# ScoreBoard-V2.net
KiCad netlist of a schematic drawn in EAGLE
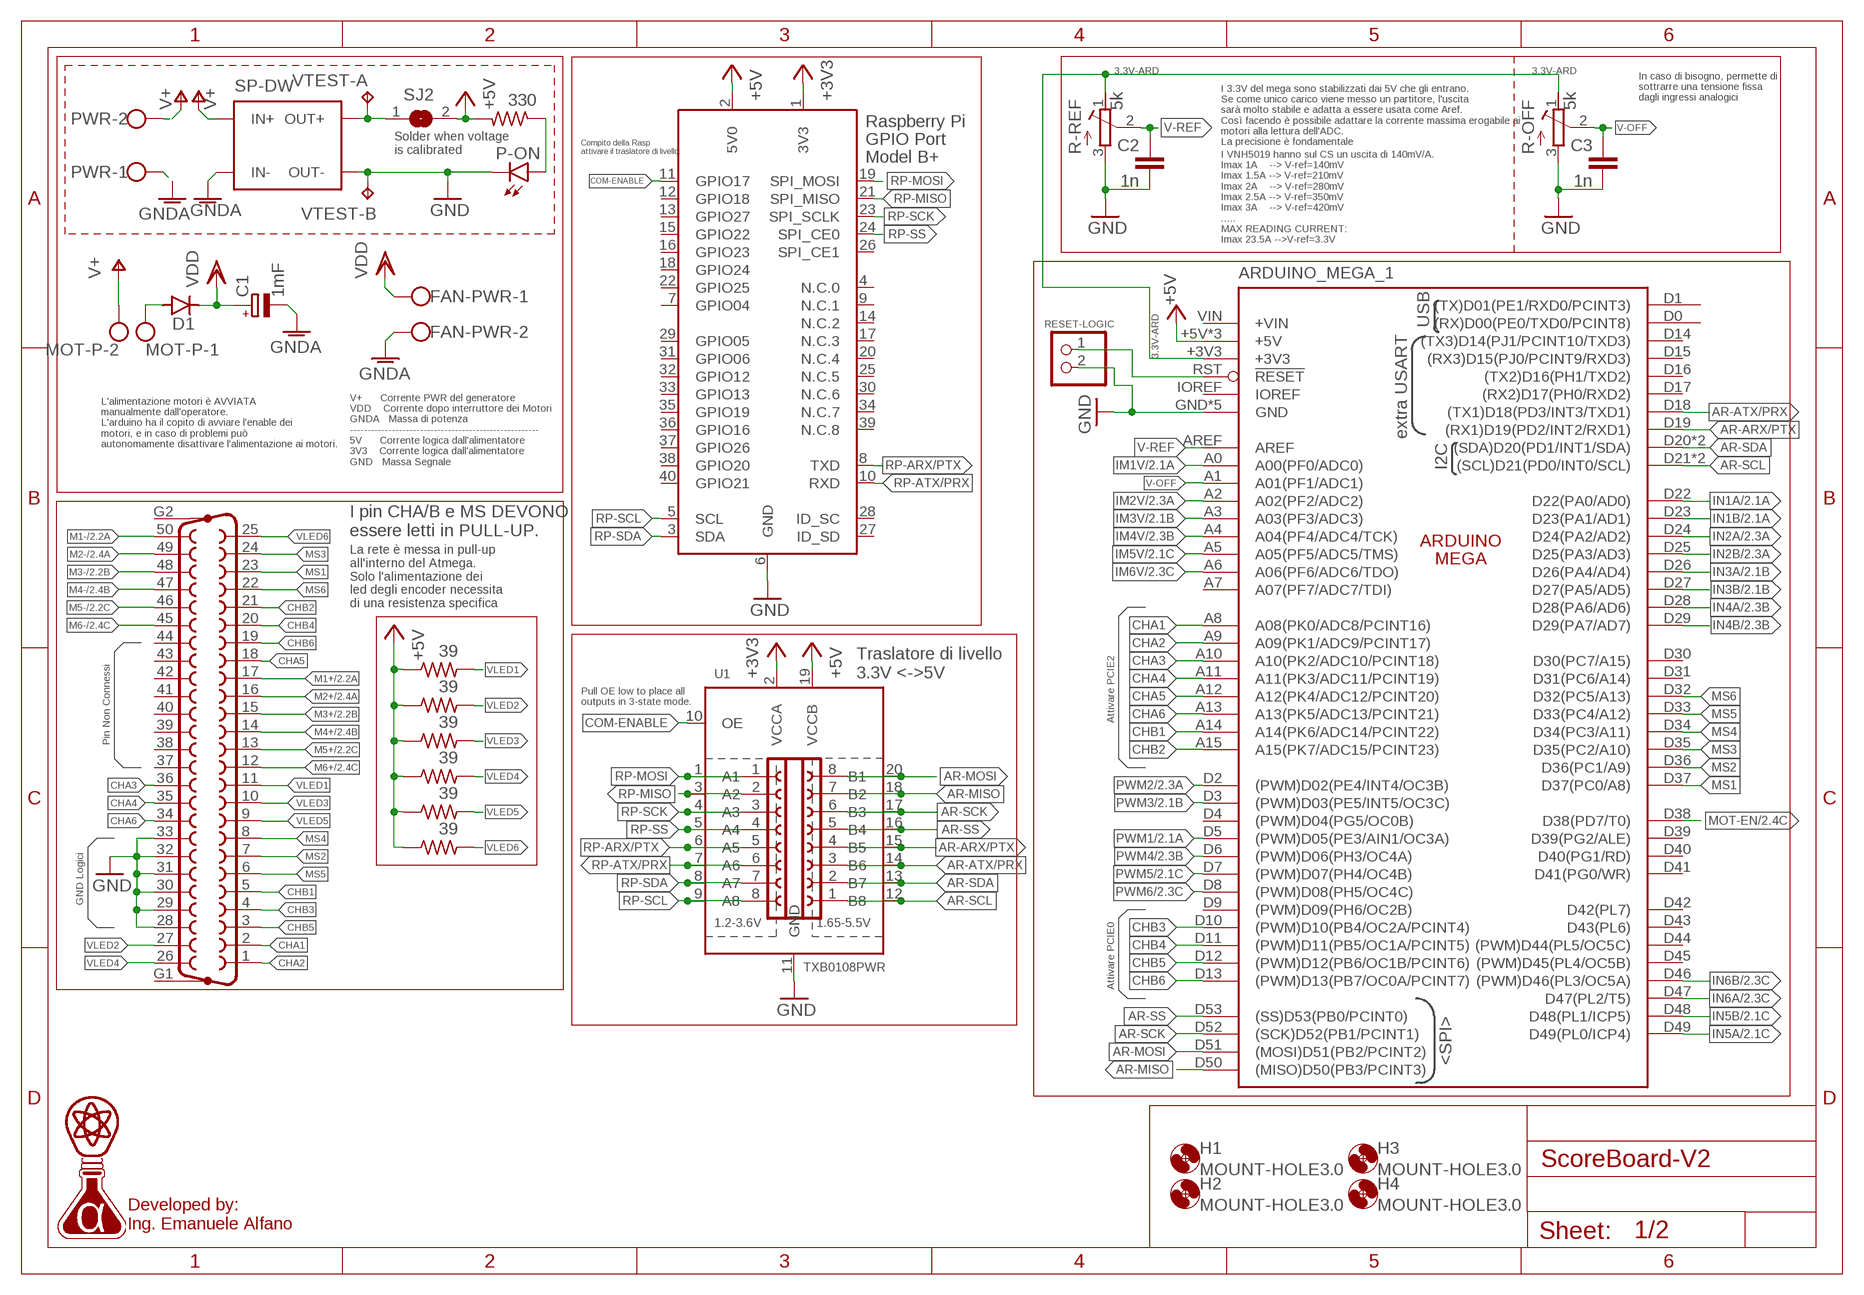
[diagram p0: schematic, sheet 1]
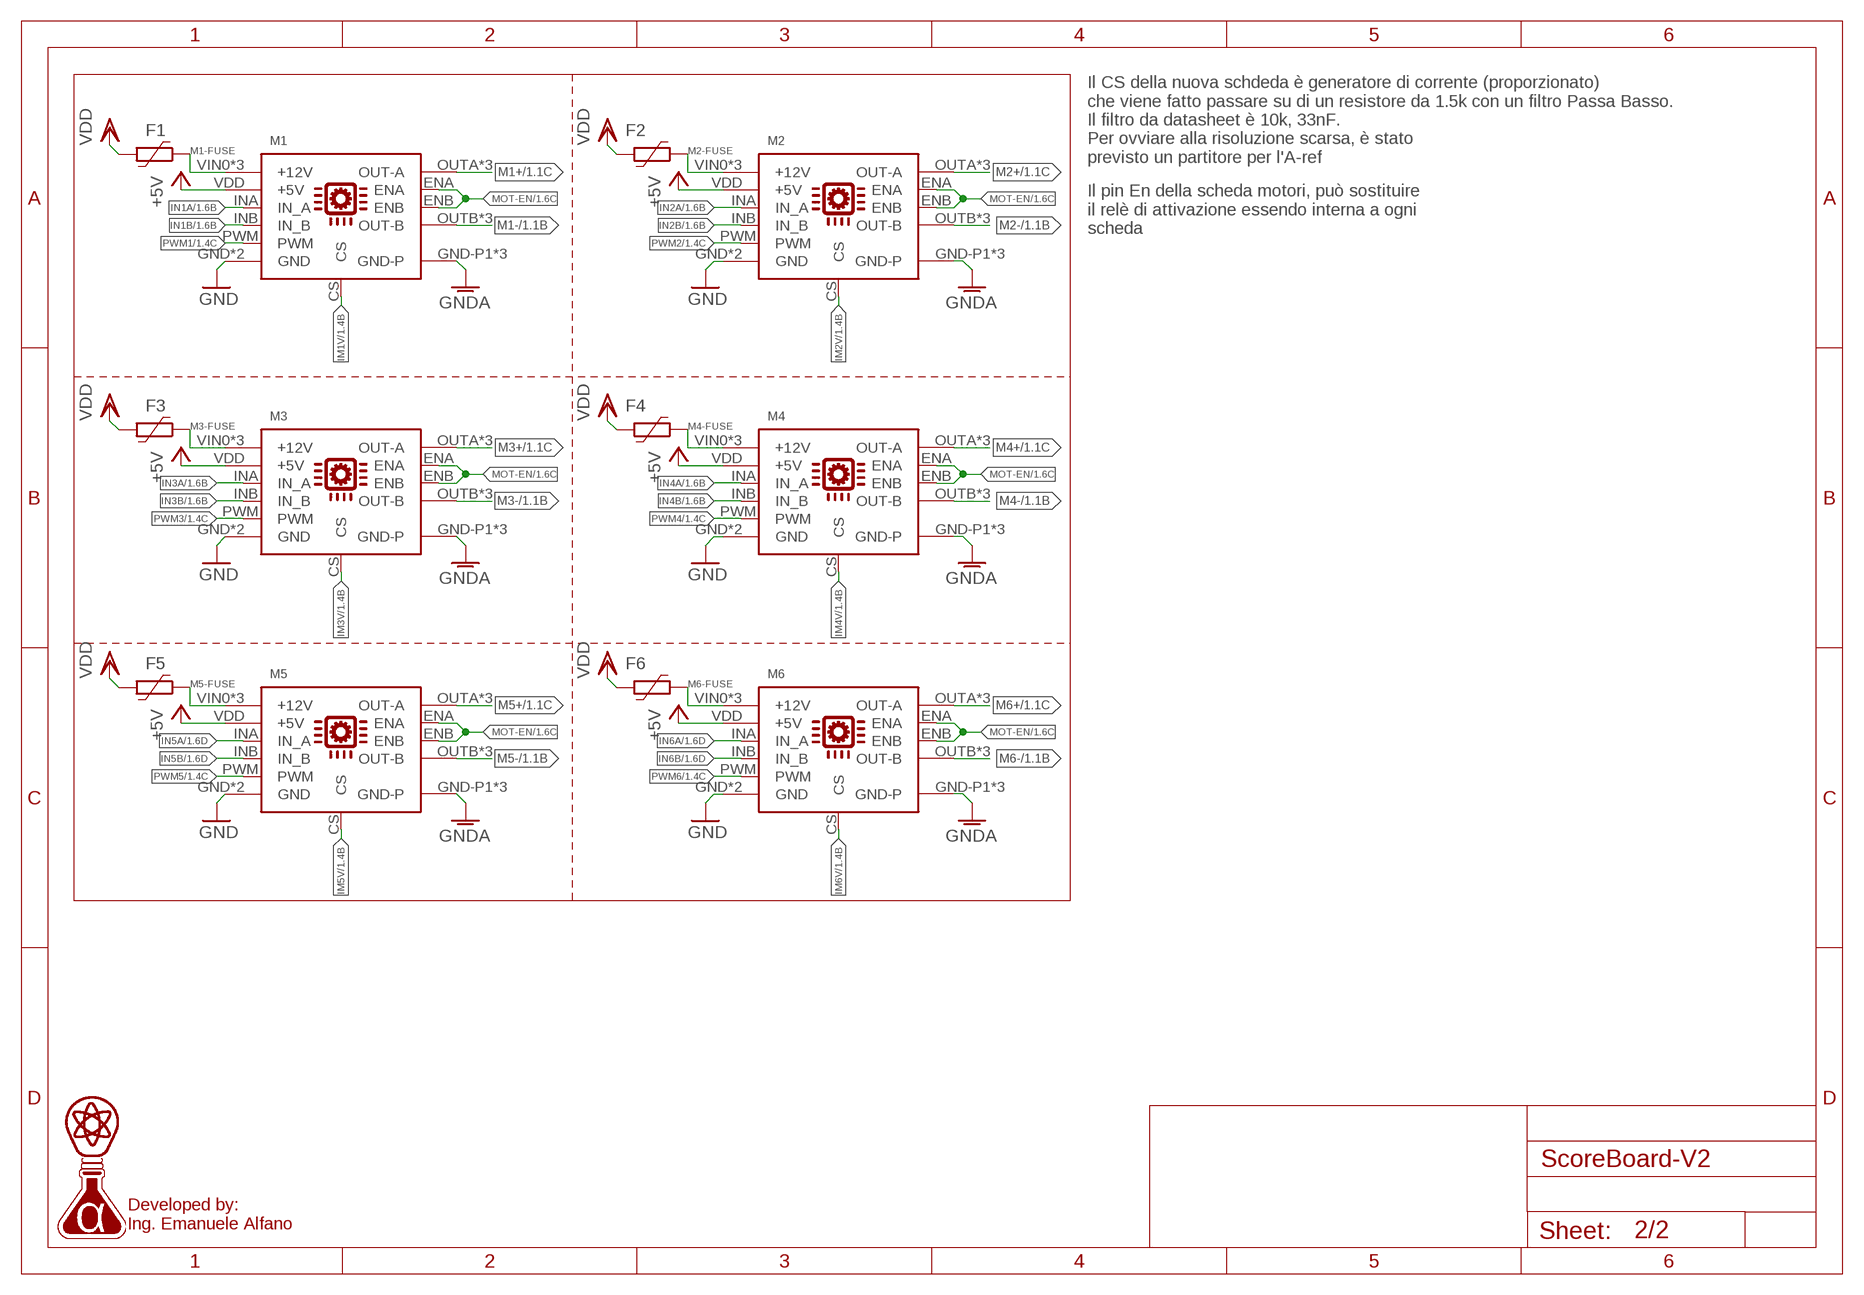
[diagram p1: schematic, sheet 2]

(export (version "E")
  (design (tool "Eeschema 10.0.6"))
  (components
    (comp (ref "ARDUINO_MEGA_1")
      (value "MEGA_ARDUINONO-HOLE")
      (footprint "eagle-import:MEGA-NO-HOLE")
      (libsource (lib "eagle-import") (part "MEGA_ARDUINONO-HOLE"))
    )
    (comp (ref "C1")
      (value "1mF")
      (footprint "eagle-import:E5-13")
      (libsource (lib "eagle-import") (part "CPOL-EUE5-13"))
    )
    (comp (ref "C2")
      (value "1n")
      (footprint "eagle-import:C025-024X044")
      (libsource (lib "eagle-import") (part "C-EU025-024X044"))
    )
    (comp (ref "C3")
      (value "1n")
      (footprint "eagle-import:C025-024X044")
      (libsource (lib "eagle-import") (part "C-EU025-024X044"))
    )
    (comp (ref "D-SUB50")
      (value "F50VP")
      (footprint "eagle-import:F50VP")
      (libsource (lib "eagle-import") (part "F50VP"))
    )
    (comp (ref "D1")
      (value "ES2D")
      (footprint "eagle-import:SMB")
      (libsource (lib "eagle-import") (part "ES2D"))
    )
    (comp (ref "FAN-PWR")
      (value "W237-102")
      (footprint "eagle-import:W237-102")
      (fields (field (name "MPN") "237-102"))
      (libsource (lib "eagle-import") (part "W237-102"))
    )
    (comp (ref "H1")
      (value "MOUNT-HOLE3.0")
      (footprint "eagle-import:3,0")
      (libsource (lib "eagle-import") (part "MOUNT-HOLE3.0"))
    )
    (comp (ref "H2")
      (value "MOUNT-HOLE3.0")
      (footprint "eagle-import:3,0")
      (libsource (lib "eagle-import") (part "MOUNT-HOLE3.0"))
    )
    (comp (ref "H3")
      (value "MOUNT-HOLE3.0")
      (footprint "eagle-import:3,0")
      (libsource (lib "eagle-import") (part "MOUNT-HOLE3.0"))
    )
    (comp (ref "H4")
      (value "MOUNT-HOLE3.0")
      (footprint "eagle-import:3,0")
      (libsource (lib "eagle-import") (part "MOUNT-HOLE3.0"))
    )
    (comp (ref "MOT-P")
      (value "W237-102")
      (footprint "eagle-import:W237-102")
      (fields (field (name "MPN") "237-102"))
      (libsource (lib "eagle-import") (part "W237-102"))
    )
    (comp (ref "P-ON")
      (value "LED3MM")
      (footprint "eagle-import:LED3MM")
      (libsource (lib "eagle-import") (part "LED3MM"))
    )
    (comp (ref "PWR")
      (value "W237-102")
      (footprint "eagle-import:W237-102")
      (fields (field (name "MPN") "237-102"))
      (libsource (lib "eagle-import") (part "W237-102"))
    )
    (comp (ref "R-OFF")
      (value "5k")
      (footprint "eagle-import:RTRIMT93YA")
      (libsource (lib "eagle-import") (part "R-TRIMMT93YA"))
    )
    (comp (ref "R-REF")
      (value "5k")
      (footprint "eagle-import:RTRIMT93YA")
      (libsource (lib "eagle-import") (part "R-TRIMMT93YA"))
    )
    (comp (ref "R1")
      (value "39")
      (footprint "eagle-import:0204_5")
      (libsource (lib "eagle-import") (part "R-US_0204/5"))
    )
    (comp (ref "R2")
      (value "39")
      (footprint "eagle-import:0204_5")
      (libsource (lib "eagle-import") (part "R-US_0204/5"))
    )
    (comp (ref "R3")
      (value "39")
      (footprint "eagle-import:0204_5")
      (libsource (lib "eagle-import") (part "R-US_0204/5"))
    )
    (comp (ref "R4")
      (value "39")
      (footprint "eagle-import:0204_5")
      (libsource (lib "eagle-import") (part "R-US_0204/5"))
    )
    (comp (ref "R5")
      (value "39")
      (footprint "eagle-import:0204_5")
      (libsource (lib "eagle-import") (part "R-US_0204/5"))
    )
    (comp (ref "R6")
      (value "39")
      (footprint "eagle-import:0204_5")
      (libsource (lib "eagle-import") (part "R-US_0204/5"))
    )
    (comp (ref "RASPBERRY-PY")
      (value "RASPI_GPIO_B+_BOX")
      (footprint "eagle-import:RASPI_GPIO_B+_BOX")
      (libsource (lib "eagle-import") (part "RASPI_GPIO_B+_BOX"))
    )
    (comp (ref "RESET-LOGIC")
      (value "PINHD-1X2")
      (footprint "eagle-import:1X02")
      (libsource (lib "eagle-import") (part "PINHD-1X2"))
    )
    (comp (ref "RL")
      (value "330")
      (footprint "eagle-import:0204_7")
      (libsource (lib "eagle-import") (part "R-US_0204/7"))
    )
    (comp (ref "SJ2")
      (value "SJ")
      (footprint "eagle-import:SJ")
      (fields (field (name "SPICEPREFIX") "B"))
      (libsource (lib "eagle-import") (part "SJ"))
    )
    (comp (ref "SP-DW")
      (value "DC/DC-STEP-DOWNGLOB")
      (footprint "eagle-import:DC_DC-STEP-DOWN-UNIVERSAL")
      (libsource (lib "eagle-import") (part "DC/DC-STEP-DOWNGLOB"))
    )
    (comp (ref "SV1")
      (value "FE08-1")
      (footprint "eagle-import:FE08")
      (libsource (lib "eagle-import") (part "FE08-1"))
    )
    (comp (ref "SV2")
      (value "FE08-1")
      (footprint "eagle-import:FE08")
      (libsource (lib "eagle-import") (part "FE08-1"))
    )
    (comp (ref "U1")
      (value "TXB0108PWR")
      (footprint "eagle-import:TSSOP20")
      (fields (field (name "MF") "Texas Instruments"))
      (libsource (lib "eagle-import") (part "TXB0108PWR"))
    )
    (comp (ref "VTEST-")
      (value "TP2P2-38-17")
      (footprint "eagle-import:P2-38-17")
      (fields (field (name "SPICEPREFIX") "X"))
      (libsource (lib "eagle-import") (part "TP2P2-38-17"))
    )
    (comp (ref "F1")
      (value "2410-BOX")
      (footprint "eagle-import:BELFUSE0679-3000-12")
      (libsource (lib "eagle-import") (part "?2410-BOX"))
    )
    (comp (ref "F2")
      (value "2410-BOX")
      (footprint "eagle-import:BELFUSE0679-3000-12")
      (libsource (lib "eagle-import") (part "?2410-BOX"))
    )
    (comp (ref "F3")
      (value "2410-BOX")
      (footprint "eagle-import:BELFUSE0679-3000-12")
      (libsource (lib "eagle-import") (part "?2410-BOX"))
    )
    (comp (ref "F4")
      (value "2410-BOX")
      (footprint "eagle-import:BELFUSE0679-3000-12")
      (libsource (lib "eagle-import") (part "?2410-BOX"))
    )
    (comp (ref "F5")
      (value "2410-BOX")
      (footprint "eagle-import:BELFUSE0679-3000-12")
      (libsource (lib "eagle-import") (part "?2410-BOX"))
    )
    (comp (ref "F6")
      (value "2410-BOX")
      (footprint "eagle-import:BELFUSE0679-3000-12")
      (libsource (lib "eagle-import") (part "?2410-BOX"))
    )
    (comp (ref "M1")
      (value "VNH5019")
      (footprint "eagle-import:VNH5019")
      (libsource (lib "eagle-import") (part "VNH5019"))
    )
    (comp (ref "M2")
      (value "VNH5019")
      (footprint "eagle-import:VNH5019")
      (libsource (lib "eagle-import") (part "VNH5019"))
    )
    (comp (ref "M3")
      (value "VNH5019")
      (footprint "eagle-import:VNH5019")
      (libsource (lib "eagle-import") (part "VNH5019"))
    )
    (comp (ref "M4")
      (value "VNH5019")
      (footprint "eagle-import:VNH5019")
      (libsource (lib "eagle-import") (part "VNH5019"))
    )
    (comp (ref "M5")
      (value "VNH5019")
      (footprint "eagle-import:VNH5019")
      (libsource (lib "eagle-import") (part "VNH5019"))
    )
    (comp (ref "M6")
      (value "VNH5019")
      (footprint "eagle-import:VNH5019")
      (libsource (lib "eagle-import") (part "VNH5019"))
    )
  )
  (nets
    (net (code "1") (name "+3V3") (class "Default")
      (node (ref "RASPBERRY-PY") (pin "1") (pinfunction "3V3_1") (pintype "power_in"))
      (node (ref "U1") (pin "2") (pinfunction "VCCA_2") (pintype "bidirectional"))
    )
    (net (code "2") (name "+5V") (class "Default")
      (node (ref "ARDUINO_MEGA_1") (pin "+5V") (pinfunction "+5V_+5V") (pintype "bidirectional"))
      (node (ref "ARDUINO_MEGA_1") (pin "+5V1") (pinfunction "+5V_+5V1") (pintype "bidirectional"))
      (node (ref "ARDUINO_MEGA_1") (pin "+5V2") (pinfunction "+5V_+5V2") (pintype "bidirectional"))
      (node (ref "M1") (pin "VDD") (pinfunction "+5V_VDD") (pintype "bidirectional"))
      (node (ref "M2") (pin "VDD") (pinfunction "+5V_VDD") (pintype "bidirectional"))
      (node (ref "M3") (pin "VDD") (pinfunction "+5V_VDD") (pintype "bidirectional"))
      (node (ref "M4") (pin "VDD") (pinfunction "+5V_VDD") (pintype "bidirectional"))
      (node (ref "M5") (pin "VDD") (pinfunction "+5V_VDD") (pintype "bidirectional"))
      (node (ref "M6") (pin "VDD") (pinfunction "+5V_VDD") (pintype "bidirectional"))
      (node (ref "R1") (pin "1") (pinfunction "1_1") (pintype "passive"))
      (node (ref "R2") (pin "1") (pinfunction "1_1") (pintype "passive"))
      (node (ref "R3") (pin "1") (pinfunction "1_1") (pintype "passive"))
      (node (ref "R4") (pin "1") (pinfunction "1_1") (pintype "passive"))
      (node (ref "R5") (pin "1") (pinfunction "1_1") (pintype "passive"))
      (node (ref "R6") (pin "1") (pinfunction "1_1") (pintype "passive"))
      (node (ref "RASPBERRY-PY") (pin "2") (pinfunction "5V0_2") (pintype "power_in"))
      (node (ref "RL") (pin "2") (pinfunction "2_2") (pintype "passive"))
      (node (ref "SJ2") (pin "2") (pinfunction "2_2") (pintype "passive"))
      (node (ref "U1") (pin "19") (pinfunction "VCCB_19") (pintype "bidirectional"))
    )
    (net (code "3") (name "3.3V-ARD") (class "Default")
      (node (ref "ARDUINO_MEGA_1") (pin "+3V3") (pinfunction "+3V3_+3V3") (pintype "bidirectional"))
      (node (ref "R-OFF") (pin "1") (pinfunction "E_1") (pintype "passive"))
      (node (ref "R-REF") (pin "1") (pinfunction "E_1") (pintype "passive"))
    )
    (net (code "4") (name "AR-ARX{slash}PTX") (class "Default")
      (node (ref "ARDUINO_MEGA_1") (pin "D19") (pinfunction "(RX1)D19(PD2/INT2/RXD1)_D19") (pintype "bidirectional"))
      (node (ref "SV2") (pin "4") (pinfunction "4_4") (pintype "passive"))
      (node (ref "U1") (pin "15") (pinfunction "B5_15") (pintype "bidirectional"))
    )
    (net (code "5") (name "AR-ATX{slash}PRX") (class "Default")
      (node (ref "ARDUINO_MEGA_1") (pin "D18") (pinfunction "(TX1)D18(PD3/INT3/TXD1)_D18") (pintype "bidirectional"))
      (node (ref "SV2") (pin "3") (pinfunction "3_3") (pintype "passive"))
      (node (ref "U1") (pin "14") (pinfunction "B6_14") (pintype "bidirectional"))
    )
    (net (code "6") (name "AR-MISO") (class "Default")
      (node (ref "ARDUINO_MEGA_1") (pin "D50") (pinfunction "(MISO)D50(PB3/PCINT3)_D50") (pintype "bidirectional"))
      (node (ref "SV2") (pin "7") (pinfunction "7_7") (pintype "passive"))
      (node (ref "U1") (pin "18") (pinfunction "B2_18") (pintype "bidirectional"))
    )
    (net (code "7") (name "AR-MOSI") (class "Default")
      (node (ref "ARDUINO_MEGA_1") (pin "D51") (pinfunction "(MOSI)D51(PB2/PCINT2)_D51") (pintype "bidirectional"))
      (node (ref "SV2") (pin "8") (pinfunction "8_8") (pintype "passive"))
      (node (ref "U1") (pin "20") (pinfunction "B1_20") (pintype "bidirectional"))
    )
    (net (code "8") (name "AR-SCK") (class "Default")
      (node (ref "ARDUINO_MEGA_1") (pin "D52") (pinfunction "(SCK)D52(PB1/PCINT1)_D52") (pintype "bidirectional"))
      (node (ref "SV2") (pin "6") (pinfunction "6_6") (pintype "passive"))
      (node (ref "U1") (pin "17") (pinfunction "B3_17") (pintype "bidirectional"))
    )
    (net (code "9") (name "AR-SCL") (class "Default")
      (node (ref "ARDUINO_MEGA_1") (pin "D21") (pinfunction "(SCL)D21(PD0/INT0/SCL)_D21") (pintype "bidirectional"))
      (node (ref "ARDUINO_MEGA_1") (pin "SCL1") (pinfunction "(SCL)D21(PD0/INT0/SCL)_SCL1") (pintype "bidirectional"))
      (node (ref "SV2") (pin "1") (pinfunction "1_1") (pintype "passive"))
      (node (ref "U1") (pin "12") (pinfunction "B8_12") (pintype "bidirectional"))
    )
    (net (code "10") (name "AR-SDA") (class "Default")
      (node (ref "ARDUINO_MEGA_1") (pin "D20") (pinfunction "(SDA)D20(PD1/INT1/SDA)_D20") (pintype "bidirectional"))
      (node (ref "ARDUINO_MEGA_1") (pin "SDA1") (pinfunction "(SDA)D20(PD1/INT1/SDA)_SDA1") (pintype "bidirectional"))
      (node (ref "SV2") (pin "2") (pinfunction "2_2") (pintype "passive"))
      (node (ref "U1") (pin "13") (pinfunction "B7_13") (pintype "bidirectional"))
    )
    (net (code "11") (name "AR-SS") (class "Default")
      (node (ref "ARDUINO_MEGA_1") (pin "D53") (pinfunction "(SS)D53(PB0/PCINT0)_D53") (pintype "bidirectional"))
      (node (ref "SV2") (pin "5") (pinfunction "5_5") (pintype "passive"))
      (node (ref "U1") (pin "16") (pinfunction "B4_16") (pintype "bidirectional"))
    )
    (net (code "12") (name "CHA1") (class "Default")
      (node (ref "ARDUINO_MEGA_1") (pin "A8") (pinfunction "A08(PK0/ADC8/PCINT16)_A8") (pintype "bidirectional"))
      (node (ref "D-SUB50") (pin "2") (pinfunction "2_2") (pintype "passive"))
    )
    (net (code "13") (name "CHA2") (class "Default")
      (node (ref "ARDUINO_MEGA_1") (pin "A9") (pinfunction "A09(PK1/ADC9/PCINT17)_A9") (pintype "bidirectional"))
      (node (ref "D-SUB50") (pin "1") (pinfunction "1_1") (pintype "passive"))
    )
    (net (code "14") (name "CHA3") (class "Default")
      (node (ref "ARDUINO_MEGA_1") (pin "A10") (pinfunction "A10(PK2/ADC10/PCINT18)_A10") (pintype "bidirectional"))
      (node (ref "D-SUB50") (pin "36") (pinfunction "36_36") (pintype "passive"))
    )
    (net (code "15") (name "CHA4") (class "Default")
      (node (ref "ARDUINO_MEGA_1") (pin "A11") (pinfunction "A11(PK3/ADC11/PCINT19)_A11") (pintype "bidirectional"))
      (node (ref "D-SUB50") (pin "35") (pinfunction "35_35") (pintype "passive"))
    )
    (net (code "16") (name "CHA5") (class "Default")
      (node (ref "ARDUINO_MEGA_1") (pin "A12") (pinfunction "A12(PK4/ADC12/PCINT20)_A12") (pintype "bidirectional"))
      (node (ref "D-SUB50") (pin "18") (pinfunction "18_18") (pintype "passive"))
    )
    (net (code "17") (name "CHA6") (class "Default")
      (node (ref "ARDUINO_MEGA_1") (pin "A13") (pinfunction "A13(PK5/ADC13/PCINT21)_A13") (pintype "bidirectional"))
      (node (ref "D-SUB50") (pin "34") (pinfunction "34_34") (pintype "passive"))
    )
    (net (code "18") (name "CHB1") (class "Default")
      (node (ref "ARDUINO_MEGA_1") (pin "A14") (pinfunction "A14(PK6/ADC14/PCINT22)_A14") (pintype "bidirectional"))
      (node (ref "D-SUB50") (pin "5") (pinfunction "5_5") (pintype "passive"))
    )
    (net (code "19") (name "CHB2") (class "Default")
      (node (ref "ARDUINO_MEGA_1") (pin "A15") (pinfunction "A15(PK7/ADC15/PCINT23)_A15") (pintype "bidirectional"))
      (node (ref "D-SUB50") (pin "21") (pinfunction "21_21") (pintype "passive"))
    )
    (net (code "20") (name "CHB3") (class "Default")
      (node (ref "ARDUINO_MEGA_1") (pin "D10") (pinfunction "(PWM)D10(PB4/OC2A/PCINT4)_D10") (pintype "bidirectional"))
      (node (ref "D-SUB50") (pin "4") (pinfunction "4_4") (pintype "passive"))
    )
    (net (code "21") (name "CHB4") (class "Default")
      (node (ref "ARDUINO_MEGA_1") (pin "D11") (pinfunction "(PWM)D11(PB5/OC1A/PCINT5)_D11") (pintype "bidirectional"))
      (node (ref "D-SUB50") (pin "20") (pinfunction "20_20") (pintype "passive"))
    )
    (net (code "22") (name "CHB5") (class "Default")
      (node (ref "ARDUINO_MEGA_1") (pin "D12") (pinfunction "(PWM)D12(PB6/OC1B/PCINT6)_D12") (pintype "bidirectional"))
      (node (ref "D-SUB50") (pin "3") (pinfunction "3_3") (pintype "passive"))
    )
    (net (code "23") (name "CHB6") (class "Default")
      (node (ref "ARDUINO_MEGA_1") (pin "D13") (pinfunction "(PWM)D13(PB7/OC0A/PCINT7)_D13") (pintype "bidirectional"))
      (node (ref "D-SUB50") (pin "19") (pinfunction "19_19") (pintype "passive"))
    )
    (net (code "24") (name "COM-ENABLE") (class "Default")
      (node (ref "RASPBERRY-PY") (pin "11") (pinfunction "GPIO17_11") (pintype "bidirectional"))
      (node (ref "U1") (pin "10") (pinfunction "OE_10") (pintype "bidirectional"))
    )
    (net (code "25") (name "GND") (class "Default")
      (node (ref "ARDUINO_MEGA_1") (pin "GND") (pinfunction "GND_GND") (pintype "bidirectional"))
      (node (ref "ARDUINO_MEGA_1") (pin "GND1") (pinfunction "GND_GND1") (pintype "bidirectional"))
      (node (ref "ARDUINO_MEGA_1") (pin "GND2") (pinfunction "GND_GND2") (pintype "bidirectional"))
      (node (ref "ARDUINO_MEGA_1") (pin "GND3") (pinfunction "GND_GND3") (pintype "bidirectional"))
      (node (ref "ARDUINO_MEGA_1") (pin "GND4") (pinfunction "GND_GND4") (pintype "bidirectional"))
      (node (ref "C2") (pin "2") (pinfunction "2_2") (pintype "passive"))
      (node (ref "C3") (pin "2") (pinfunction "2_2") (pintype "passive"))
      (node (ref "D-SUB50") (pin "28") (pinfunction "28_28") (pintype "passive"))
      (node (ref "D-SUB50") (pin "29") (pinfunction "29_29") (pintype "passive"))
      (node (ref "D-SUB50") (pin "30") (pinfunction "30_30") (pintype "passive"))
      (node (ref "D-SUB50") (pin "31") (pinfunction "31_31") (pintype "passive"))
      (node (ref "D-SUB50") (pin "32") (pinfunction "32_32") (pintype "passive"))
      (node (ref "D-SUB50") (pin "33") (pinfunction "33_33") (pintype "passive"))
      (node (ref "M1") (pin "GND") (pinfunction "GND_GND") (pintype "bidirectional"))
      (node (ref "M1") (pin "GND1") (pinfunction "GND_GND1") (pintype "bidirectional"))
      (node (ref "M2") (pin "GND") (pinfunction "GND_GND") (pintype "bidirectional"))
      (node (ref "M2") (pin "GND1") (pinfunction "GND_GND1") (pintype "bidirectional"))
      (node (ref "M3") (pin "GND") (pinfunction "GND_GND") (pintype "bidirectional"))
      (node (ref "M3") (pin "GND1") (pinfunction "GND_GND1") (pintype "bidirectional"))
      (node (ref "M4") (pin "GND") (pinfunction "GND_GND") (pintype "bidirectional"))
      (node (ref "M4") (pin "GND1") (pinfunction "GND_GND1") (pintype "bidirectional"))
      (node (ref "M5") (pin "GND") (pinfunction "GND_GND") (pintype "bidirectional"))
      (node (ref "M5") (pin "GND1") (pinfunction "GND_GND1") (pintype "bidirectional"))
      (node (ref "M6") (pin "GND") (pinfunction "GND_GND") (pintype "bidirectional"))
      (node (ref "M6") (pin "GND1") (pinfunction "GND_GND1") (pintype "bidirectional"))
      (node (ref "P-ON") (pin "K") (pinfunction "C_K") (pintype "passive"))
      (node (ref "R-OFF") (pin "3") (pinfunction "A_3") (pintype "passive"))
      (node (ref "R-REF") (pin "3") (pinfunction "A_3") (pintype "passive"))
      (node (ref "RASPBERRY-PY") (pin "6") (pinfunction "GND_6") (pintype "power_in"))
      (node (ref "RESET-LOGIC") (pin "2") (pinfunction "2_2") (pintype "passive"))
      (node (ref "SP-DW") (pin "OUT-") (pinfunction "OUT-_OUT-") (pintype "bidirectional"))
      (node (ref "SP-DW") (pin "OUT-1") (pinfunction "OUT-_OUT-1") (pintype "bidirectional"))
      (node (ref "SP-DW") (pin "OUT-2") (pinfunction "OUT-_OUT-2") (pintype "bidirectional"))
      (node (ref "U1") (pin "11") (pinfunction "GND_11") (pintype "bidirectional"))
      (node (ref "VTEST-") (pin "TP-2") (pinfunction "TP_TP-2") (pintype "input"))
    )
    (net (code "26") (name "GNDA") (class "Default")
      (node (ref "C1") (pin "-") (pinfunction "-_-") (pintype "passive"))
      (node (ref "FAN-PWR") (pin "2") (pinfunction "KL_2") (pintype "passive"))
      (node (ref "M1") (pin "GND-P1") (pinfunction "GND-P_GND-P1") (pintype "bidirectional"))
      (node (ref "M1") (pin "GND-P2") (pinfunction "GND-P_GND-P2") (pintype "bidirectional"))
      (node (ref "M1") (pin "GND-P3") (pinfunction "GND-P_GND-P3") (pintype "bidirectional"))
      (node (ref "M2") (pin "GND-P1") (pinfunction "GND-P_GND-P1") (pintype "bidirectional"))
      (node (ref "M2") (pin "GND-P2") (pinfunction "GND-P_GND-P2") (pintype "bidirectional"))
      (node (ref "M2") (pin "GND-P3") (pinfunction "GND-P_GND-P3") (pintype "bidirectional"))
      (node (ref "M3") (pin "GND-P1") (pinfunction "GND-P_GND-P1") (pintype "bidirectional"))
      (node (ref "M3") (pin "GND-P2") (pinfunction "GND-P_GND-P2") (pintype "bidirectional"))
      (node (ref "M3") (pin "GND-P3") (pinfunction "GND-P_GND-P3") (pintype "bidirectional"))
      (node (ref "M4") (pin "GND-P1") (pinfunction "GND-P_GND-P1") (pintype "bidirectional"))
      (node (ref "M4") (pin "GND-P2") (pinfunction "GND-P_GND-P2") (pintype "bidirectional"))
      (node (ref "M4") (pin "GND-P3") (pinfunction "GND-P_GND-P3") (pintype "bidirectional"))
      (node (ref "M5") (pin "GND-P1") (pinfunction "GND-P_GND-P1") (pintype "bidirectional"))
      (node (ref "M5") (pin "GND-P2") (pinfunction "GND-P_GND-P2") (pintype "bidirectional"))
      (node (ref "M5") (pin "GND-P3") (pinfunction "GND-P_GND-P3") (pintype "bidirectional"))
      (node (ref "M6") (pin "GND-P1") (pinfunction "GND-P_GND-P1") (pintype "bidirectional"))
      (node (ref "M6") (pin "GND-P2") (pinfunction "GND-P_GND-P2") (pintype "bidirectional"))
      (node (ref "M6") (pin "GND-P3") (pinfunction "GND-P_GND-P3") (pintype "bidirectional"))
      (node (ref "PWR") (pin "1") (pinfunction "KL_1") (pintype "passive"))
      (node (ref "SP-DW") (pin "IN-") (pinfunction "IN-_IN-") (pintype "bidirectional"))
      (node (ref "SP-DW") (pin "IN-1") (pinfunction "IN-_IN-1") (pintype "bidirectional"))
      (node (ref "SP-DW") (pin "IN-2") (pinfunction "IN-_IN-2") (pintype "bidirectional"))
    )
    (net (code "27") (name "IM1V") (class "Default")
      (node (ref "ARDUINO_MEGA_1") (pin "A0") (pinfunction "A00(PF0/ADC0)_A0") (pintype "bidirectional"))
      (node (ref "M1") (pin "CS") (pinfunction "CS_CS") (pintype "bidirectional"))
    )
    (net (code "28") (name "IM2V") (class "Default")
      (node (ref "ARDUINO_MEGA_1") (pin "A2") (pinfunction "A02(PF2/ADC2)_A2") (pintype "bidirectional"))
      (node (ref "M2") (pin "CS") (pinfunction "CS_CS") (pintype "bidirectional"))
    )
    (net (code "29") (name "IM3V") (class "Default")
      (node (ref "ARDUINO_MEGA_1") (pin "A3") (pinfunction "A03(PF3/ADC3)_A3") (pintype "bidirectional"))
      (node (ref "M3") (pin "CS") (pinfunction "CS_CS") (pintype "bidirectional"))
    )
    (net (code "30") (name "IM4V") (class "Default")
      (node (ref "ARDUINO_MEGA_1") (pin "A4") (pinfunction "A04(PF4/ADC4/TCK)_A4") (pintype "bidirectional"))
      (node (ref "M4") (pin "CS") (pinfunction "CS_CS") (pintype "bidirectional"))
    )
    (net (code "31") (name "IM5V") (class "Default")
      (node (ref "ARDUINO_MEGA_1") (pin "A5") (pinfunction "A05(PF5/ADC5/TMS)_A5") (pintype "bidirectional"))
      (node (ref "M5") (pin "CS") (pinfunction "CS_CS") (pintype "bidirectional"))
    )
    (net (code "32") (name "IM6V") (class "Default")
      (node (ref "ARDUINO_MEGA_1") (pin "A6") (pinfunction "A06(PF6/ADC6/TDO)_A6") (pintype "bidirectional"))
      (node (ref "M6") (pin "CS") (pinfunction "CS_CS") (pintype "bidirectional"))
    )
    (net (code "33") (name "IN1A") (class "Default")
      (node (ref "ARDUINO_MEGA_1") (pin "D22") (pinfunction "D22(PA0/AD0)_D22") (pintype "bidirectional"))
      (node (ref "M1") (pin "INA") (pinfunction "IN_A_INA") (pintype "bidirectional"))
    )
    (net (code "34") (name "IN1B") (class "Default")
      (node (ref "ARDUINO_MEGA_1") (pin "D23") (pinfunction "D23(PA1/AD1)_D23") (pintype "bidirectional"))
      (node (ref "M1") (pin "INB") (pinfunction "IN_B_INB") (pintype "bidirectional"))
    )
    (net (code "35") (name "IN2A") (class "Default")
      (node (ref "ARDUINO_MEGA_1") (pin "D24") (pinfunction "D24(PA2/AD2)_D24") (pintype "bidirectional"))
      (node (ref "M2") (pin "INA") (pinfunction "IN_A_INA") (pintype "bidirectional"))
    )
    (net (code "36") (name "IN2B") (class "Default")
      (node (ref "ARDUINO_MEGA_1") (pin "D25") (pinfunction "D25(PA3/AD3)_D25") (pintype "bidirectional"))
      (node (ref "M2") (pin "INB") (pinfunction "IN_B_INB") (pintype "bidirectional"))
    )
    (net (code "37") (name "IN3A") (class "Default")
      (node (ref "ARDUINO_MEGA_1") (pin "D26") (pinfunction "D26(PA4/AD4)_D26") (pintype "bidirectional"))
      (node (ref "M3") (pin "INA") (pinfunction "IN_A_INA") (pintype "bidirectional"))
    )
    (net (code "38") (name "IN3B") (class "Default")
      (node (ref "ARDUINO_MEGA_1") (pin "D27") (pinfunction "D27(PA5/AD5)_D27") (pintype "bidirectional"))
      (node (ref "M3") (pin "INB") (pinfunction "IN_B_INB") (pintype "bidirectional"))
    )
    (net (code "39") (name "IN4A") (class "Default")
      (node (ref "ARDUINO_MEGA_1") (pin "D28") (pinfunction "D28(PA6/AD6)_D28") (pintype "bidirectional"))
      (node (ref "M4") (pin "INA") (pinfunction "IN_A_INA") (pintype "bidirectional"))
    )
    (net (code "40") (name "IN4B") (class "Default")
      (node (ref "ARDUINO_MEGA_1") (pin "D29") (pinfunction "D29(PA7/AD7)_D29") (pintype "bidirectional"))
      (node (ref "M4") (pin "INB") (pinfunction "IN_B_INB") (pintype "bidirectional"))
    )
    (net (code "41") (name "IN5A") (class "Default")
      (node (ref "ARDUINO_MEGA_1") (pin "D49") (pinfunction "D49(PL0/ICP4)_D49") (pintype "bidirectional"))
      (node (ref "M5") (pin "INA") (pinfunction "IN_A_INA") (pintype "bidirectional"))
    )
    (net (code "42") (name "IN5B") (class "Default")
      (node (ref "ARDUINO_MEGA_1") (pin "D48") (pinfunction "D48(PL1/ICP5)_D48") (pintype "bidirectional"))
      (node (ref "M5") (pin "INB") (pinfunction "IN_B_INB") (pintype "bidirectional"))
    )
    (net (code "43") (name "IN6A") (class "Default")
      (node (ref "ARDUINO_MEGA_1") (pin "D47") (pinfunction "D47(PL2/T5)_D47") (pintype "bidirectional"))
      (node (ref "M6") (pin "INA") (pinfunction "IN_A_INA") (pintype "bidirectional"))
    )
    (net (code "44") (name "IN6B") (class "Default")
      (node (ref "ARDUINO_MEGA_1") (pin "D46") (pinfunction "(PWM)D46(PL3/OC5A)_D46") (pintype "bidirectional"))
      (node (ref "M6") (pin "INB") (pinfunction "IN_B_INB") (pintype "bidirectional"))
    )
    (net (code "45") (name "M1+") (class "Default")
      (node (ref "D-SUB50") (pin "17") (pinfunction "17_17") (pintype "passive"))
      (node (ref "M1") (pin "OUTA") (pinfunction "OUT-A_OUTA") (pintype "bidirectional"))
      (node (ref "M1") (pin "OUTA2") (pinfunction "OUT-A_OUTA2") (pintype "bidirectional"))
      (node (ref "M1") (pin "OUTA3") (pinfunction "OUT-A_OUTA3") (pintype "bidirectional"))
    )
    (net (code "46") (name "M1-") (class "Default")
      (node (ref "D-SUB50") (pin "50") (pinfunction "50_50") (pintype "passive"))
      (node (ref "M1") (pin "OUTB") (pinfunction "OUT-B_OUTB") (pintype "bidirectional"))
      (node (ref "M1") (pin "OUTB1") (pinfunction "OUT-B_OUTB1") (pintype "bidirectional"))
      (node (ref "M1") (pin "OUTB3") (pinfunction "OUT-B_OUTB3") (pintype "bidirectional"))
    )
    (net (code "47") (name "M1-FUSE") (class "Default")
      (node (ref "F1") (pin "1") (pinfunction "1_1") (pintype "passive"))
      (node (ref "M1") (pin "VIN0") (pinfunction "+12V_VIN0") (pintype "bidirectional"))
      (node (ref "M1") (pin "VIN1") (pinfunction "+12V_VIN1") (pintype "bidirectional"))
      (node (ref "M1") (pin "VIN2") (pinfunction "+12V_VIN2") (pintype "bidirectional"))
    )
    (net (code "48") (name "M2+") (class "Default")
      (node (ref "D-SUB50") (pin "16") (pinfunction "16_16") (pintype "passive"))
      (node (ref "M2") (pin "OUTA") (pinfunction "OUT-A_OUTA") (pintype "bidirectional"))
      (node (ref "M2") (pin "OUTA2") (pinfunction "OUT-A_OUTA2") (pintype "bidirectional"))
      (node (ref "M2") (pin "OUTA3") (pinfunction "OUT-A_OUTA3") (pintype "bidirectional"))
    )
    (net (code "49") (name "M2-") (class "Default")
      (node (ref "D-SUB50") (pin "49") (pinfunction "49_49") (pintype "passive"))
      (node (ref "M2") (pin "OUTB") (pinfunction "OUT-B_OUTB") (pintype "bidirectional"))
      (node (ref "M2") (pin "OUTB1") (pinfunction "OUT-B_OUTB1") (pintype "bidirectional"))
      (node (ref "M2") (pin "OUTB3") (pinfunction "OUT-B_OUTB3") (pintype "bidirectional"))
    )
    (net (code "50") (name "M2-FUSE") (class "Default")
      (node (ref "F2") (pin "1") (pinfunction "1_1") (pintype "passive"))
      (node (ref "M2") (pin "VIN0") (pinfunction "+12V_VIN0") (pintype "bidirectional"))
      (node (ref "M2") (pin "VIN1") (pinfunction "+12V_VIN1") (pintype "bidirectional"))
      (node (ref "M2") (pin "VIN2") (pinfunction "+12V_VIN2") (pintype "bidirectional"))
    )
    (net (code "51") (name "M3+") (class "Default")
      (node (ref "D-SUB50") (pin "15") (pinfunction "15_15") (pintype "passive"))
      (node (ref "M3") (pin "OUTA") (pinfunction "OUT-A_OUTA") (pintype "bidirectional"))
      (node (ref "M3") (pin "OUTA2") (pinfunction "OUT-A_OUTA2") (pintype "bidirectional"))
      (node (ref "M3") (pin "OUTA3") (pinfunction "OUT-A_OUTA3") (pintype "bidirectional"))
    )
    (net (code "52") (name "M3-") (class "Default")
      (node (ref "D-SUB50") (pin "48") (pinfunction "48_48") (pintype "passive"))
      (node (ref "M3") (pin "OUTB") (pinfunction "OUT-B_OUTB") (pintype "bidirectional"))
      (node (ref "M3") (pin "OUTB1") (pinfunction "OUT-B_OUTB1") (pintype "bidirectional"))
      (node (ref "M3") (pin "OUTB3") (pinfunction "OUT-B_OUTB3") (pintype "bidirectional"))
    )
    (net (code "53") (name "M3-FUSE") (class "Default")
      (node (ref "F3") (pin "1") (pinfunction "1_1") (pintype "passive"))
      (node (ref "M3") (pin "VIN0") (pinfunction "+12V_VIN0") (pintype "bidirectional"))
      (node (ref "M3") (pin "VIN1") (pinfunction "+12V_VIN1") (pintype "bidirectional"))
      (node (ref "M3") (pin "VIN2") (pinfunction "+12V_VIN2") (pintype "bidirectional"))
    )
    (net (code "54") (name "M4+") (class "Default")
      (node (ref "D-SUB50") (pin "14") (pinfunction "14_14") (pintype "passive"))
      (node (ref "M4") (pin "OUTA") (pinfunction "OUT-A_OUTA") (pintype "bidirectional"))
      (node (ref "M4") (pin "OUTA2") (pinfunction "OUT-A_OUTA2") (pintype "bidirectional"))
      (node (ref "M4") (pin "OUTA3") (pinfunction "OUT-A_OUTA3") (pintype "bidirectional"))
    )
    (net (code "55") (name "M4-") (class "Default")
      (node (ref "D-SUB50") (pin "47") (pinfunction "47_47") (pintype "passive"))
      (node (ref "M4") (pin "OUTB") (pinfunction "OUT-B_OUTB") (pintype "bidirectional"))
      (node (ref "M4") (pin "OUTB1") (pinfunction "OUT-B_OUTB1") (pintype "bidirectional"))
      (node (ref "M4") (pin "OUTB3") (pinfunction "OUT-B_OUTB3") (pintype "bidirectional"))
    )
    (net (code "56") (name "M4-FUSE") (class "Default")
      (node (ref "F4") (pin "1") (pinfunction "1_1") (pintype "passive"))
      (node (ref "M4") (pin "VIN0") (pinfunction "+12V_VIN0") (pintype "bidirectional"))
      (node (ref "M4") (pin "VIN1") (pinfunction "+12V_VIN1") (pintype "bidirectional"))
      (node (ref "M4") (pin "VIN2") (pinfunction "+12V_VIN2") (pintype "bidirectional"))
    )
    (net (code "57") (name "M5+") (class "Default")
      (node (ref "D-SUB50") (pin "13") (pinfunction "13_13") (pintype "passive"))
      (node (ref "M5") (pin "OUTA") (pinfunction "OUT-A_OUTA") (pintype "bidirectional"))
      (node (ref "M5") (pin "OUTA2") (pinfunction "OUT-A_OUTA2") (pintype "bidirectional"))
      (node (ref "M5") (pin "OUTA3") (pinfunction "OUT-A_OUTA3") (pintype "bidirectional"))
    )
    (net (code "58") (name "M5-") (class "Default")
      (node (ref "D-SUB50") (pin "46") (pinfunction "46_46") (pintype "passive"))
      (node (ref "M5") (pin "OUTB") (pinfunction "OUT-B_OUTB") (pintype "bidirectional"))
      (node (ref "M5") (pin "OUTB1") (pinfunction "OUT-B_OUTB1") (pintype "bidirectional"))
      (node (ref "M5") (pin "OUTB3") (pinfunction "OUT-B_OUTB3") (pintype "bidirectional"))
    )
    (net (code "59") (name "M5-FUSE") (class "Default")
      (node (ref "F5") (pin "1") (pinfunction "1_1") (pintype "passive"))
      (node (ref "M5") (pin "VIN0") (pinfunction "+12V_VIN0") (pintype "bidirectional"))
      (node (ref "M5") (pin "VIN1") (pinfunction "+12V_VIN1") (pintype "bidirectional"))
      (node (ref "M5") (pin "VIN2") (pinfunction "+12V_VIN2") (pintype "bidirectional"))
    )
    (net (code "60") (name "M6+") (class "Default")
      (node (ref "D-SUB50") (pin "12") (pinfunction "12_12") (pintype "passive"))
      (node (ref "M6") (pin "OUTA") (pinfunction "OUT-A_OUTA") (pintype "bidirectional"))
      (node (ref "M6") (pin "OUTA2") (pinfunction "OUT-A_OUTA2") (pintype "bidirectional"))
      (node (ref "M6") (pin "OUTA3") (pinfunction "OUT-A_OUTA3") (pintype "bidirectional"))
    )
    (net (code "61") (name "M6-") (class "Default")
      (node (ref "D-SUB50") (pin "45") (pinfunction "45_45") (pintype "passive"))
      (node (ref "M6") (pin "OUTB") (pinfunction "OUT-B_OUTB") (pintype "bidirectional"))
      (node (ref "M6") (pin "OUTB1") (pinfunction "OUT-B_OUTB1") (pintype "bidirectional"))
      (node (ref "M6") (pin "OUTB3") (pinfunction "OUT-B_OUTB3") (pintype "bidirectional"))
    )
    (net (code "62") (name "M6-FUSE") (class "Default")
      (node (ref "F6") (pin "1") (pinfunction "1_1") (pintype "passive"))
      (node (ref "M6") (pin "VIN0") (pinfunction "+12V_VIN0") (pintype "bidirectional"))
      (node (ref "M6") (pin "VIN1") (pinfunction "+12V_VIN1") (pintype "bidirectional"))
      (node (ref "M6") (pin "VIN2") (pinfunction "+12V_VIN2") (pintype "bidirectional"))
    )
    (net (code "63") (name "MOT-EN") (class "Default")
      (node (ref "ARDUINO_MEGA_1") (pin "D38") (pinfunction "D38(PD7/T0)_D38") (pintype "bidirectional"))
      (node (ref "M1") (pin "ENA") (pinfunction "ENA_ENA") (pintype "bidirectional"))
      (node (ref "M1") (pin "ENB") (pinfunction "ENB_ENB") (pintype "bidirectional"))
      (node (ref "M2") (pin "ENA") (pinfunction "ENA_ENA") (pintype "bidirectional"))
      (node (ref "M2") (pin "ENB") (pinfunction "ENB_ENB") (pintype "bidirectional"))
      (node (ref "M3") (pin "ENA") (pinfunction "ENA_ENA") (pintype "bidirectional"))
      (node (ref "M3") (pin "ENB") (pinfunction "ENB_ENB") (pintype "bidirectional"))
      (node (ref "M4") (pin "ENA") (pinfunction "ENA_ENA") (pintype "bidirectional"))
      (node (ref "M4") (pin "ENB") (pinfunction "ENB_ENB") (pintype "bidirectional"))
      (node (ref "M5") (pin "ENA") (pinfunction "ENA_ENA") (pintype "bidirectional"))
      (node (ref "M5") (pin "ENB") (pinfunction "ENB_ENB") (pintype "bidirectional"))
      (node (ref "M6") (pin "ENA") (pinfunction "ENA_ENA") (pintype "bidirectional"))
      (node (ref "M6") (pin "ENB") (pinfunction "ENB_ENB") (pintype "bidirectional"))
    )
    (net (code "64") (name "MS1") (class "Default")
      (node (ref "ARDUINO_MEGA_1") (pin "D37") (pinfunction "D37(PC0/A8)_D37") (pintype "bidirectional"))
      (node (ref "D-SUB50") (pin "23") (pinfunction "23_23") (pintype "passive"))
    )
    (net (code "65") (name "MS2") (class "Default")
      (node (ref "ARDUINO_MEGA_1") (pin "D36") (pinfunction "D36(PC1/A9)_D36") (pintype "bidirectional"))
      (node (ref "D-SUB50") (pin "7") (pinfunction "7_7") (pintype "passive"))
    )
    (net (code "66") (name "MS3") (class "Default")
      (node (ref "ARDUINO_MEGA_1") (pin "D35") (pinfunction "D35(PC2/A10)_D35") (pintype "bidirectional"))
      (node (ref "D-SUB50") (pin "24") (pinfunction "24_24") (pintype "passive"))
    )
    (net (code "67") (name "MS4") (class "Default")
      (node (ref "ARDUINO_MEGA_1") (pin "D34") (pinfunction "D34(PC3/A11)_D34") (pintype "bidirectional"))
      (node (ref "D-SUB50") (pin "8") (pinfunction "8_8") (pintype "passive"))
    )
    (net (code "68") (name "MS5") (class "Default")
      (node (ref "ARDUINO_MEGA_1") (pin "D33") (pinfunction "D33(PC4/A12)_D33") (pintype "bidirectional"))
      (node (ref "D-SUB50") (pin "6") (pinfunction "6_6") (pintype "passive"))
    )
    (net (code "69") (name "MS6") (class "Default")
      (node (ref "ARDUINO_MEGA_1") (pin "D32") (pinfunction "D32(PC5/A13)_D32") (pintype "bidirectional"))
      (node (ref "D-SUB50") (pin "22") (pinfunction "22_22") (pintype "passive"))
    )
    (net (code "70") (name "Net-(ARDUINO_MEGA_1-~{RESET})") (class "Default")
      (node (ref "ARDUINO_MEGA_1") (pin "RST") (pinfunction "~{RESET}_RST") (pintype "bidirectional"))
      (node (ref "RESET-LOGIC") (pin "1") (pinfunction "1_1") (pintype "passive"))
    )
    (net (code "71") (name "Net-(MOT-PA-KL)") (class "Default")
      (node (ref "D1") (pin "A") (pinfunction "A_A") (pintype "passive"))
      (node (ref "MOT-P") (pin "1") (pinfunction "KL_1") (pintype "passive"))
    )
    (net (code "72") (name "Net-(P-ON-PadA)") (class "Default")
      (node (ref "P-ON") (pin "A") (pinfunction "A_A") (pintype "passive"))
      (node (ref "RL") (pin "1") (pinfunction "1_1") (pintype "passive"))
    )
    (net (code "73") (name "Net-(VTEST-A-TP)") (class "Default")
      (node (ref "SJ2") (pin "1") (pinfunction "1_1") (pintype "passive"))
      (node (ref "SP-DW") (pin "OUT+") (pinfunction "OUT+_OUT+") (pintype "bidirectional"))
      (node (ref "SP-DW") (pin "OUT+1") (pinfunction "OUT+_OUT+1") (pintype "bidirectional"))
      (node (ref "SP-DW") (pin "OUT+2") (pinfunction "OUT+_OUT+2") (pintype "bidirectional"))
      (node (ref "VTEST-") (pin "TP-1") (pinfunction "TP_TP-1") (pintype "input"))
    )
    (net (code "74") (name "PWM1") (class "Default")
      (node (ref "ARDUINO_MEGA_1") (pin "D5") (pinfunction "(PWM)D05(PE3/AIN1/OC3A)_D5") (pintype "bidirectional"))
      (node (ref "M1") (pin "PWM") (pinfunction "PWM_PWM") (pintype "bidirectional"))
    )
    (net (code "75") (name "PWM2") (class "Default")
      (node (ref "ARDUINO_MEGA_1") (pin "D2") (pinfunction "(PWM)D02(PE4/INT4/OC3B)_D2") (pintype "bidirectional"))
      (node (ref "M2") (pin "PWM") (pinfunction "PWM_PWM") (pintype "bidirectional"))
    )
    (net (code "76") (name "PWM3") (class "Default")
      (node (ref "ARDUINO_MEGA_1") (pin "D3") (pinfunction "(PWM)D03(PE5/INT5/OC3C)_D3") (pintype "bidirectional"))
      (node (ref "M3") (pin "PWM") (pinfunction "PWM_PWM") (pintype "bidirectional"))
    )
    (net (code "77") (name "PWM4") (class "Default")
      (node (ref "ARDUINO_MEGA_1") (pin "D6") (pinfunction "(PWM)D06(PH3/OC4A)_D6") (pintype "bidirectional"))
      (node (ref "M4") (pin "PWM") (pinfunction "PWM_PWM") (pintype "bidirectional"))
    )
    (net (code "78") (name "PWM5") (class "Default")
      (node (ref "ARDUINO_MEGA_1") (pin "D7") (pinfunction "(PWM)D07(PH4/OC4B)_D7") (pintype "bidirectional"))
      (node (ref "M5") (pin "PWM") (pinfunction "PWM_PWM") (pintype "bidirectional"))
    )
    (net (code "79") (name "PWM6") (class "Default")
      (node (ref "ARDUINO_MEGA_1") (pin "D8") (pinfunction "(PWM)D08(PH5/OC4C)_D8") (pintype "bidirectional"))
      (node (ref "M6") (pin "PWM") (pinfunction "PWM_PWM") (pintype "bidirectional"))
    )
    (net (code "80") (name "RP-ARX{slash}PTX") (class "Default")
      (node (ref "RASPBERRY-PY") (pin "8") (pinfunction "TXD_8") (pintype "bidirectional"))
      (node (ref "SV1") (pin "5") (pinfunction "5_5") (pintype "passive"))
      (node (ref "U1") (pin "6") (pinfunction "A5_6") (pintype "bidirectional"))
    )
    (net (code "81") (name "RP-ATX{slash}PRX") (class "Default")
      (node (ref "RASPBERRY-PY") (pin "10") (pinfunction "RXD_10") (pintype "bidirectional"))
      (node (ref "SV1") (pin "6") (pinfunction "6_6") (pintype "passive"))
      (node (ref "U1") (pin "7") (pinfunction "A6_7") (pintype "bidirectional"))
    )
    (net (code "82") (name "RP-MISO") (class "Default")
      (node (ref "RASPBERRY-PY") (pin "21") (pinfunction "SPI_MISO_21") (pintype "bidirectional"))
      (node (ref "SV1") (pin "2") (pinfunction "2_2") (pintype "passive"))
      (node (ref "U1") (pin "3") (pinfunction "A2_3") (pintype "bidirectional"))
    )
    (net (code "83") (name "RP-MOSI") (class "Default")
      (node (ref "RASPBERRY-PY") (pin "19") (pinfunction "SPI_MOSI_19") (pintype "bidirectional"))
      (node (ref "SV1") (pin "1") (pinfunction "1_1") (pintype "passive"))
      (node (ref "U1") (pin "1") (pinfunction "A1_1") (pintype "bidirectional"))
    )
    (net (code "84") (name "RP-SCK") (class "Default")
      (node (ref "RASPBERRY-PY") (pin "23") (pinfunction "SPI_SCLK_23") (pintype "bidirectional"))
      (node (ref "SV1") (pin "3") (pinfunction "3_3") (pintype "passive"))
      (node (ref "U1") (pin "4") (pinfunction "A3_4") (pintype "bidirectional"))
    )
    (net (code "85") (name "RP-SCL") (class "Default")
      (node (ref "RASPBERRY-PY") (pin "5") (pinfunction "SCL_5") (pintype "bidirectional"))
      (node (ref "SV1") (pin "8") (pinfunction "8_8") (pintype "passive"))
      (node (ref "U1") (pin "9") (pinfunction "A8_9") (pintype "bidirectional"))
    )
    (net (code "86") (name "RP-SDA") (class "Default")
      (node (ref "RASPBERRY-PY") (pin "3") (pinfunction "SDA_3") (pintype "bidirectional"))
      (node (ref "SV1") (pin "7") (pinfunction "7_7") (pintype "passive"))
      (node (ref "U1") (pin "8") (pinfunction "A7_8") (pintype "bidirectional"))
    )
    (net (code "87") (name "RP-SS") (class "Default")
      (node (ref "RASPBERRY-PY") (pin "24") (pinfunction "SPI_CE0_24") (pintype "bidirectional"))
      (node (ref "SV1") (pin "4") (pinfunction "4_4") (pintype "passive"))
      (node (ref "U1") (pin "5") (pinfunction "A4_5") (pintype "bidirectional"))
    )
    (net (code "88") (name "V+") (class "Default")
      (node (ref "MOT-P") (pin "2") (pinfunction "KL_2") (pintype "passive"))
      (node (ref "PWR") (pin "2") (pinfunction "KL_2") (pintype "passive"))
      (node (ref "SP-DW") (pin "IN+") (pinfunction "IN+_IN+") (pintype "bidirectional"))
      (node (ref "SP-DW") (pin "IN+1") (pinfunction "IN+_IN+1") (pintype "bidirectional"))
      (node (ref "SP-DW") (pin "IN+2") (pinfunction "IN+_IN+2") (pintype "bidirectional"))
    )
    (net (code "89") (name "V-OFF") (class "Default")
      (node (ref "ARDUINO_MEGA_1") (pin "A1") (pinfunction "A01(PF1/ADC1)_A1") (pintype "bidirectional"))
      (node (ref "C3") (pin "1") (pinfunction "1_1") (pintype "passive"))
      (node (ref "R-OFF") (pin "2") (pinfunction "S_2") (pintype "passive"))
    )
    (net (code "90") (name "V-REF") (class "Default")
      (node (ref "ARDUINO_MEGA_1") (pin "AREF") (pinfunction "AREF_AREF") (pintype "bidirectional"))
      (node (ref "C2") (pin "1") (pinfunction "1_1") (pintype "passive"))
      (node (ref "R-REF") (pin "2") (pinfunction "S_2") (pintype "passive"))
    )
    (net (code "91") (name "VDD") (class "Default")
      (node (ref "C1") (pin "+") (pinfunction "+_+") (pintype "passive"))
      (node (ref "D1") (pin "C") (pinfunction "C_C") (pintype "passive"))
      (node (ref "F1") (pin "2") (pinfunction "2_2") (pintype "passive"))
      (node (ref "F2") (pin "2") (pinfunction "2_2") (pintype "passive"))
      (node (ref "F3") (pin "2") (pinfunction "2_2") (pintype "passive"))
      (node (ref "F4") (pin "2") (pinfunction "2_2") (pintype "passive"))
      (node (ref "F5") (pin "2") (pinfunction "2_2") (pintype "passive"))
      (node (ref "F6") (pin "2") (pinfunction "2_2") (pintype "passive"))
      (node (ref "FAN-PWR") (pin "1") (pinfunction "KL_1") (pintype "passive"))
    )
    (net (code "92") (name "VLED1") (class "Default")
      (node (ref "D-SUB50") (pin "11") (pinfunction "11_11") (pintype "passive"))
      (node (ref "R1") (pin "2") (pinfunction "2_2") (pintype "passive"))
    )
    (net (code "93") (name "VLED2") (class "Default")
      (node (ref "D-SUB50") (pin "27") (pinfunction "27_27") (pintype "passive"))
      (node (ref "R2") (pin "2") (pinfunction "2_2") (pintype "passive"))
    )
    (net (code "94") (name "VLED3") (class "Default")
      (node (ref "D-SUB50") (pin "10") (pinfunction "10_10") (pintype "passive"))
      (node (ref "R3") (pin "2") (pinfunction "2_2") (pintype "passive"))
    )
    (net (code "95") (name "VLED4") (class "Default")
      (node (ref "D-SUB50") (pin "26") (pinfunction "26_26") (pintype "passive"))
      (node (ref "R4") (pin "2") (pinfunction "2_2") (pintype "passive"))
    )
    (net (code "96") (name "VLED5") (class "Default")
      (node (ref "D-SUB50") (pin "9") (pinfunction "9_9") (pintype "passive"))
      (node (ref "R5") (pin "2") (pinfunction "2_2") (pintype "passive"))
    )
    (net (code "97") (name "VLED6") (class "Default")
      (node (ref "D-SUB50") (pin "25") (pinfunction "25_25") (pintype "passive"))
      (node (ref "R6") (pin "2") (pinfunction "2_2") (pintype "passive"))
    )
    (net (code "98") (name "unconnected-(ARDUINO_MEGA_1-(PWM)D04(PG5{slash}OC0B)-PadD4)") (class "Default")
      (node (ref "ARDUINO_MEGA_1") (pin "D4") (pinfunction "(PWM)D04(PG5/OC0B)_D4") (pintype "bidirectional"))
    )
    (net (code "99") (name "unconnected-(ARDUINO_MEGA_1-(PWM)D09(PH6{slash}OC2B)-PadD9)") (class "Default")
      (node (ref "ARDUINO_MEGA_1") (pin "D9") (pinfunction "(PWM)D09(PH6/OC2B)_D9") (pintype "bidirectional"))
    )
    (net (code "100") (name "unconnected-(ARDUINO_MEGA_1-(PWM)D44(PL5{slash}OC5C)-PadD44)") (class "Default")
      (node (ref "ARDUINO_MEGA_1") (pin "D44") (pinfunction "(PWM)D44(PL5/OC5C)_D44") (pintype "bidirectional"))
    )
    (net (code "101") (name "unconnected-(ARDUINO_MEGA_1-(PWM)D45(PL4{slash}OC5B)-PadD45)") (class "Default")
      (node (ref "ARDUINO_MEGA_1") (pin "D45") (pinfunction "(PWM)D45(PL4/OC5B)_D45") (pintype "bidirectional"))
    )
    (net (code "102") (name "unconnected-(ARDUINO_MEGA_1-(RX)D00(PE0{slash}TXD0{slash}PCINT8)-PadD0)") (class "Default")
      (node (ref "ARDUINO_MEGA_1") (pin "D0") (pinfunction "(RX)D00(PE0/TXD0/PCINT8)_D0") (pintype "bidirectional"))
    )
    (net (code "103") (name "unconnected-(ARDUINO_MEGA_1-(RX2)D17(PH0{slash}RXD2)-PadD17)") (class "Default")
      (node (ref "ARDUINO_MEGA_1") (pin "D17") (pinfunction "(RX2)D17(PH0/RXD2)_D17") (pintype "bidirectional"))
    )
    (net (code "104") (name "unconnected-(ARDUINO_MEGA_1-(RX3)D15(PJ0{slash}PCINT9{slash}RXD3)-PadD15)") (class "Default")
      (node (ref "ARDUINO_MEGA_1") (pin "D15") (pinfunction "(RX3)D15(PJ0/PCINT9/RXD3)_D15") (pintype "bidirectional"))
    )
    (net (code "105") (name "unconnected-(ARDUINO_MEGA_1-(TX)D01(PE1{slash}RXD0{slash}PCINT3)-PadD1)") (class "Default")
      (node (ref "ARDUINO_MEGA_1") (pin "D1") (pinfunction "(TX)D01(PE1/RXD0/PCINT3)_D1") (pintype "bidirectional"))
    )
    (net (code "106") (name "unconnected-(ARDUINO_MEGA_1-(TX2)D16(PH1{slash}TXD2)-PadD16)") (class "Default")
      (node (ref "ARDUINO_MEGA_1") (pin "D16") (pinfunction "(TX2)D16(PH1/TXD2)_D16") (pintype "bidirectional"))
    )
    (net (code "107") (name "unconnected-(ARDUINO_MEGA_1-(TX3)D14(PJ1{slash}PCINT10{slash}TXD3)-PadD14)") (class "Default")
      (node (ref "ARDUINO_MEGA_1") (pin "D14") (pinfunction "(TX3)D14(PJ1/PCINT10/TXD3)_D14") (pintype "bidirectional"))
    )
    (net (code "108") (name "unconnected-(ARDUINO_MEGA_1-+VIN-PadVIN)") (class "Default")
      (node (ref "ARDUINO_MEGA_1") (pin "VIN") (pinfunction "+VIN_VIN") (pintype "bidirectional"))
    )
    (net (code "109") (name "unconnected-(ARDUINO_MEGA_1-A07(PF7{slash}ADC7{slash}TDI)-PadA7)") (class "Default")
      (node (ref "ARDUINO_MEGA_1") (pin "A7") (pinfunction "A07(PF7/ADC7/TDI)_A7") (pintype "bidirectional"))
    )
    (net (code "110") (name "unconnected-(ARDUINO_MEGA_1-D30(PC7{slash}A15)-PadD30)") (class "Default")
      (node (ref "ARDUINO_MEGA_1") (pin "D30") (pinfunction "D30(PC7/A15)_D30") (pintype "bidirectional"))
    )
    (net (code "111") (name "unconnected-(ARDUINO_MEGA_1-D31(PC6{slash}A14)-PadD31)") (class "Default")
      (node (ref "ARDUINO_MEGA_1") (pin "D31") (pinfunction "D31(PC6/A14)_D31") (pintype "bidirectional"))
    )
    (net (code "112") (name "unconnected-(ARDUINO_MEGA_1-D39(PG2{slash}ALE)-PadD39)") (class "Default")
      (node (ref "ARDUINO_MEGA_1") (pin "D39") (pinfunction "D39(PG2/ALE)_D39") (pintype "bidirectional"))
    )
    (net (code "113") (name "unconnected-(ARDUINO_MEGA_1-D40(PG1{slash}RD)-PadD40)") (class "Default")
      (node (ref "ARDUINO_MEGA_1") (pin "D40") (pinfunction "D40(PG1/RD)_D40") (pintype "bidirectional"))
    )
    (net (code "114") (name "unconnected-(ARDUINO_MEGA_1-D41(PG0{slash}WR)-PadD41)") (class "Default")
      (node (ref "ARDUINO_MEGA_1") (pin "D41") (pinfunction "D41(PG0/WR)_D41") (pintype "bidirectional"))
    )
    (net (code "115") (name "unconnected-(ARDUINO_MEGA_1-D42(PL7)-PadD42)") (class "Default")
      (node (ref "ARDUINO_MEGA_1") (pin "D42") (pinfunction "D42(PL7)_D42") (pintype "bidirectional"))
    )
    (net (code "116") (name "unconnected-(ARDUINO_MEGA_1-D43(PL6)-PadD43)") (class "Default")
      (node (ref "ARDUINO_MEGA_1") (pin "D43") (pinfunction "D43(PL6)_D43") (pintype "bidirectional"))
    )
    (net (code "117") (name "unconnected-(ARDUINO_MEGA_1-PadIOREF)") (class "Default")
      (node (ref "ARDUINO_MEGA_1") (pin "IOREF") (pinfunction "IOREF_IOREF") (pintype "bidirectional"))
    )
    (net (code "118") (name "unconnected-(D-SUB50-Pad37)") (class "Default")
      (node (ref "D-SUB50") (pin "37") (pinfunction "37_37") (pintype "passive"))
    )
    (net (code "119") (name "unconnected-(D-SUB50-Pad38)") (class "Default")
      (node (ref "D-SUB50") (pin "38") (pinfunction "38_38") (pintype "passive"))
    )
    (net (code "120") (name "unconnected-(D-SUB50-Pad39)") (class "Default")
      (node (ref "D-SUB50") (pin "39") (pinfunction "39_39") (pintype "passive"))
    )
    (net (code "121") (name "unconnected-(D-SUB50-Pad40)") (class "Default")
      (node (ref "D-SUB50") (pin "40") (pinfunction "40_40") (pintype "passive"))
    )
    (net (code "122") (name "unconnected-(D-SUB50-Pad41)") (class "Default")
      (node (ref "D-SUB50") (pin "41") (pinfunction "41_41") (pintype "passive"))
    )
    (net (code "123") (name "unconnected-(D-SUB50-Pad42)") (class "Default")
      (node (ref "D-SUB50") (pin "42") (pinfunction "42_42") (pintype "passive"))
    )
    (net (code "124") (name "unconnected-(D-SUB50-Pad43)") (class "Default")
      (node (ref "D-SUB50") (pin "43") (pinfunction "43_43") (pintype "passive"))
    )
    (net (code "125") (name "unconnected-(D-SUB50-Pad44)") (class "Default")
      (node (ref "D-SUB50") (pin "44") (pinfunction "44_44") (pintype "passive"))
    )
    (net (code "126") (name "unconnected-(D-SUB50-PadG1)") (class "Default")
      (node (ref "D-SUB50") (pin "G1") (pinfunction "G1_G1") (pintype "passive"))
    )
    (net (code "127") (name "unconnected-(D-SUB50-PadG2)") (class "Default")
      (node (ref "D-SUB50") (pin "G2") (pinfunction "G2_G2") (pintype "passive"))
    )
    (net (code "128") (name "unconnected-(RASPBERRY-PY-GPIO04-Pad7)") (class "Default")
      (node (ref "RASPBERRY-PY") (pin "7") (pinfunction "GPIO04_7") (pintype "bidirectional"))
    )
    (net (code "129") (name "unconnected-(RASPBERRY-PY-GPIO05-Pad29)") (class "Default")
      (node (ref "RASPBERRY-PY") (pin "29") (pinfunction "GPIO05_29") (pintype "no_connect"))
    )
    (net (code "130") (name "unconnected-(RASPBERRY-PY-GPIO06-Pad31)") (class "Default")
      (node (ref "RASPBERRY-PY") (pin "31") (pinfunction "GPIO06_31") (pintype "no_connect"))
    )
    (net (code "131") (name "unconnected-(RASPBERRY-PY-GPIO12-Pad32)") (class "Default")
      (node (ref "RASPBERRY-PY") (pin "32") (pinfunction "GPIO12_32") (pintype "no_connect"))
    )
    (net (code "132") (name "unconnected-(RASPBERRY-PY-GPIO13-Pad33)") (class "Default")
      (node (ref "RASPBERRY-PY") (pin "33") (pinfunction "GPIO13_33") (pintype "no_connect"))
    )
    (net (code "133") (name "unconnected-(RASPBERRY-PY-GPIO16-Pad36)") (class "Default")
      (node (ref "RASPBERRY-PY") (pin "36") (pinfunction "GPIO16_36") (pintype "no_connect"))
    )
    (net (code "134") (name "unconnected-(RASPBERRY-PY-GPIO18-Pad12)") (class "Default")
      (node (ref "RASPBERRY-PY") (pin "12") (pinfunction "GPIO18_12") (pintype "bidirectional"))
    )
    (net (code "135") (name "unconnected-(RASPBERRY-PY-GPIO19-Pad35)") (class "Default")
      (node (ref "RASPBERRY-PY") (pin "35") (pinfunction "GPIO19_35") (pintype "no_connect"))
    )
    (net (code "136") (name "unconnected-(RASPBERRY-PY-GPIO20-Pad38)") (class "Default")
      (node (ref "RASPBERRY-PY") (pin "38") (pinfunction "GPIO20_38") (pintype "no_connect"))
    )
    (net (code "137") (name "unconnected-(RASPBERRY-PY-GPIO21-Pad40)") (class "Default")
      (node (ref "RASPBERRY-PY") (pin "40") (pinfunction "GPIO21_40") (pintype "no_connect"))
    )
    (net (code "138") (name "unconnected-(RASPBERRY-PY-GPIO22-Pad15)") (class "Default")
      (node (ref "RASPBERRY-PY") (pin "15") (pinfunction "GPIO22_15") (pintype "bidirectional"))
    )
    (net (code "139") (name "unconnected-(RASPBERRY-PY-GPIO23-Pad16)") (class "Default")
      (node (ref "RASPBERRY-PY") (pin "16") (pinfunction "GPIO23_16") (pintype "bidirectional"))
    )
    (net (code "140") (name "unconnected-(RASPBERRY-PY-GPIO24-Pad18)") (class "Default")
      (node (ref "RASPBERRY-PY") (pin "18") (pinfunction "GPIO24_18") (pintype "bidirectional"))
    )
    (net (code "141") (name "unconnected-(RASPBERRY-PY-GPIO25-Pad22)") (class "Default")
      (node (ref "RASPBERRY-PY") (pin "22") (pinfunction "GPIO25_22") (pintype "bidirectional"))
    )
    (net (code "142") (name "unconnected-(RASPBERRY-PY-GPIO26-Pad37)") (class "Default")
      (node (ref "RASPBERRY-PY") (pin "37") (pinfunction "GPIO26_37") (pintype "no_connect"))
    )
    (net (code "143") (name "unconnected-(RASPBERRY-PY-GPIO27-Pad13)") (class "Default")
      (node (ref "RASPBERRY-PY") (pin "13") (pinfunction "GPIO27_13") (pintype "bidirectional"))
    )
    (net (code "144") (name "unconnected-(RASPBERRY-PY-ID_SC-Pad28)") (class "Default")
      (node (ref "RASPBERRY-PY") (pin "28") (pinfunction "ID_SC_28") (pintype "no_connect"))
    )
    (net (code "145") (name "unconnected-(RASPBERRY-PY-ID_SD-Pad27)") (class "Default")
      (node (ref "RASPBERRY-PY") (pin "27") (pinfunction "ID_SD_27") (pintype "no_connect"))
    )
    (net (code "146") (name "unconnected-(RASPBERRY-PY-N.C.0-Pad4)") (class "Default")
      (node (ref "RASPBERRY-PY") (pin "4") (pinfunction "N.C.0_4") (pintype "no_connect"))
    )
    (net (code "147") (name "unconnected-(RASPBERRY-PY-N.C.1-Pad9)") (class "Default")
      (node (ref "RASPBERRY-PY") (pin "9") (pinfunction "N.C.1_9") (pintype "no_connect"))
    )
    (net (code "148") (name "unconnected-(RASPBERRY-PY-N.C.2-Pad14)") (class "Default")
      (node (ref "RASPBERRY-PY") (pin "14") (pinfunction "N.C.2_14") (pintype "no_connect"))
    )
    (net (code "149") (name "unconnected-(RASPBERRY-PY-N.C.3-Pad17)") (class "Default")
      (node (ref "RASPBERRY-PY") (pin "17") (pinfunction "N.C.3_17") (pintype "no_connect"))
    )
    (net (code "150") (name "unconnected-(RASPBERRY-PY-N.C.4-Pad20)") (class "Default")
      (node (ref "RASPBERRY-PY") (pin "20") (pinfunction "N.C.4_20") (pintype "no_connect"))
    )
    (net (code "151") (name "unconnected-(RASPBERRY-PY-N.C.5-Pad25)") (class "Default")
      (node (ref "RASPBERRY-PY") (pin "25") (pinfunction "N.C.5_25") (pintype "no_connect"))
    )
    (net (code "152") (name "unconnected-(RASPBERRY-PY-N.C.6-Pad30)") (class "Default")
      (node (ref "RASPBERRY-PY") (pin "30") (pinfunction "N.C.6_30") (pintype "no_connect"))
    )
    (net (code "153") (name "unconnected-(RASPBERRY-PY-N.C.7-Pad34)") (class "Default")
      (node (ref "RASPBERRY-PY") (pin "34") (pinfunction "N.C.7_34") (pintype "no_connect"))
    )
    (net (code "154") (name "unconnected-(RASPBERRY-PY-N.C.8-Pad39)") (class "Default")
      (node (ref "RASPBERRY-PY") (pin "39") (pinfunction "N.C.8_39") (pintype "no_connect"))
    )
    (net (code "155") (name "unconnected-(RASPBERRY-PY-SPI_CE1-Pad26)") (class "Default")
      (node (ref "RASPBERRY-PY") (pin "26") (pinfunction "SPI_CE1_26") (pintype "bidirectional"))
    )
  )
)
